# design.net
KiCad netlist of a schematic drawn in Altium Designer
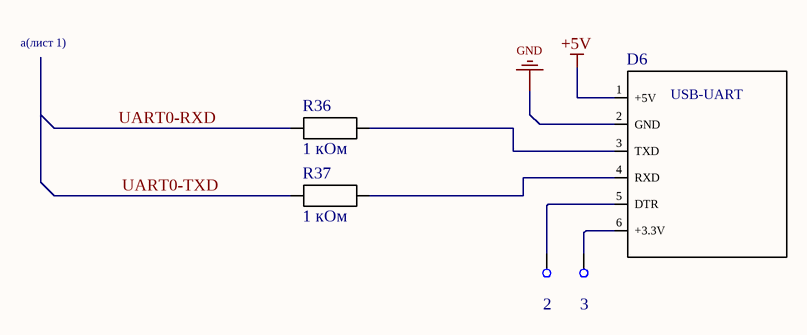
[diagram p0: Программаторы.SchDoc]

(export (version "E")
  (design (tool "Eeschema 10.0.6"))
  (components
    (comp (ref "2") (value "~") (footprint "PAD0,7X1.5") (libsource (lib "РАЗЪЕМЫ") (part "КП_0,7Х1,5")))
    (comp (ref "3") (value "~") (footprint "PAD0,7X1.5") (libsource (lib "РАЗЪЕМЫ") (part "КП_0,7Х1,5")))
    (comp (ref "D6")
      (value "~")
      (footprint "USB-UART-CP2102")
      (fields (field (name "MANUFACTURER") "China") (field (name "MANUFACTURERPARTNUMBER") "CJMUC CP2102"))
      (libsource (lib "МИКРОСХЕМЫ") (part "USB-UART"))
    )
    (comp (ref "R36")
      (value "1 кОм")
      (footprint "Р1-12-0,125")
      (fields
        (field (name "TOLERANCE") "±1%-Л")
        (field (name "PARTNUMBER") "АЛЯР.434110.005 ТУ")
        (field (name "MANUFACTURERPARTNUMBER") "Р1-12-0,125-10,0 кОм±1%-Л")
      )
      (libsource (lib "РЕЗИСТОРЫ") (part "Р1-12-0,125-10,0 кОм±1%"))
    )
    (comp (ref "R37")
      (value "1 кОм")
      (footprint "Р1-12-0,125")
      (fields
        (field (name "TOLERANCE") "±1%-Л")
        (field (name "PARTNUMBER") "АЛЯР.434110.005 ТУ")
        (field (name "MANUFACTURERPARTNUMBER") "Р1-12-0,125-10,0 кОм±1%-Л")
      )
      (libsource (lib "РЕЗИСТОРЫ") (part "Р1-12-0,125-10,0 кОм±1%"))
    )
  )
  (nets
    (net (code "1") (name "+5V") (class "Default")
      (node (ref "D6") (pin "1") (pinfunction "+5V_1") (pintype "passive"))
    )
    (net (code "2") (name "/UART0-RXD") (class "Default")
      (node (ref "R36") (pin "1") (pinfunction "1_1") (pintype "passive"))
    )
    (net (code "3") (name "/UART0-TXD") (class "Default")
      (node (ref "R37") (pin "1") (pinfunction "1_1") (pintype "passive"))
    )
    (net (code "4") (name "GND") (class "Default")
      (node (ref "D6") (pin "2") (pinfunction "GND_2") (pintype "passive"))
    )
    (net (code "5") (name "Net-(D6-+3.3V)") (class "Default")
      (node (ref "3") (pin "1") (pinfunction "1_1") (pintype "passive"))
      (node (ref "D6") (pin "6") (pinfunction "+3.3V_6") (pintype "passive"))
    )
    (net (code "6") (name "Net-(D6-DTR)") (class "Default")
      (node (ref "2") (pin "1") (pinfunction "1_1") (pintype "passive"))
      (node (ref "D6") (pin "5") (pinfunction "DTR_5") (pintype "passive"))
    )
    (net (code "7") (name "Net-(D6-RXD)") (class "Default")
      (node (ref "D6") (pin "4") (pinfunction "RXD_4") (pintype "passive"))
      (node (ref "R37") (pin "2") (pinfunction "2_2") (pintype "passive"))
    )
    (net (code "8") (name "Net-(D6-TXD)") (class "Default")
      (node (ref "D6") (pin "3") (pinfunction "TXD_3") (pintype "passive"))
      (node (ref "R36") (pin "2") (pinfunction "2_2") (pintype "passive"))
    )
  )
)
